# right_revision0_6.net
KiCad netlist of a schematic drawn in EAGLE
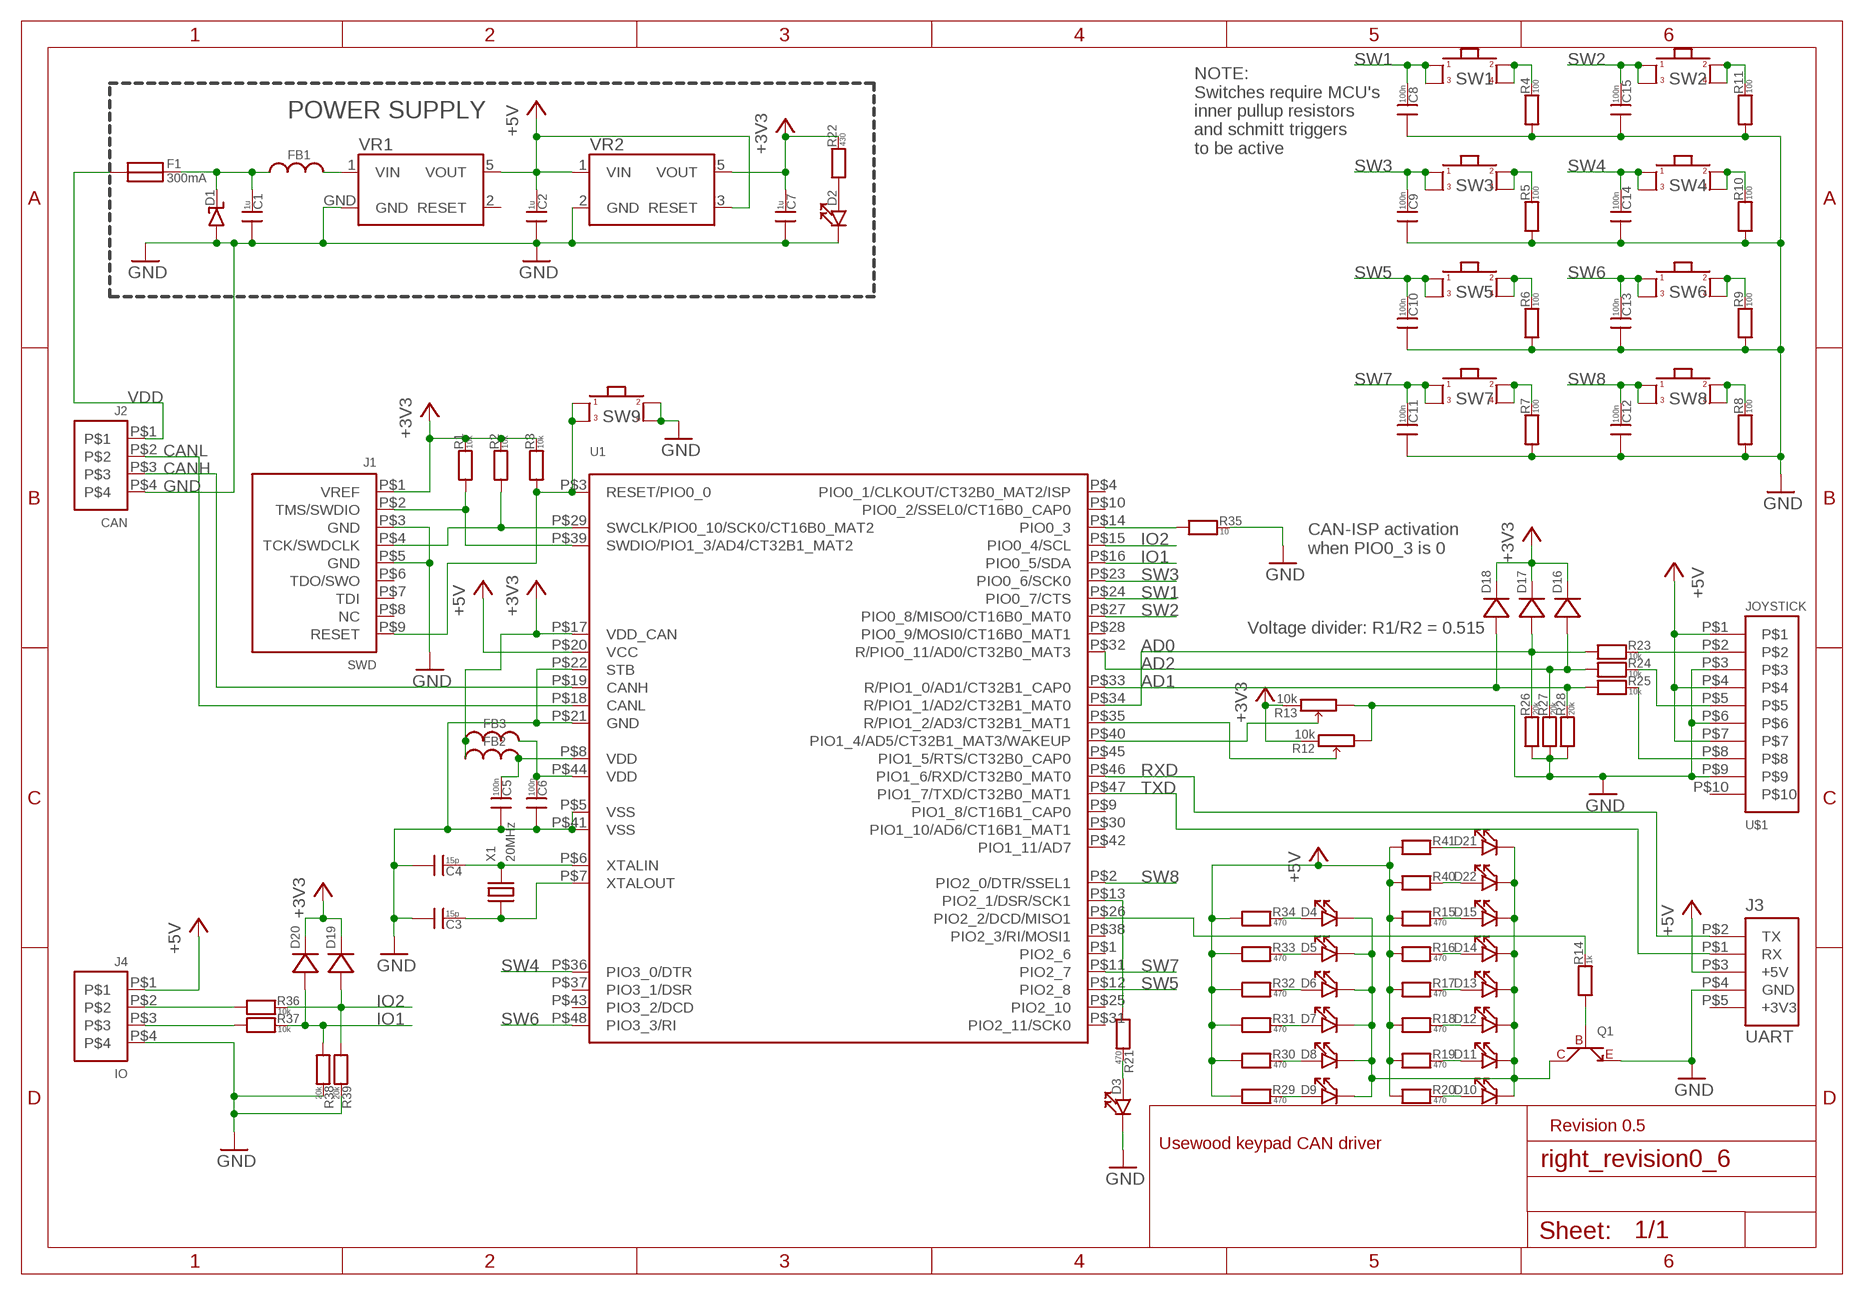
[diagram p0: schematic, sheet 1]

(export (version "E")
  (design (tool "Eeschema 10.0.6"))
  (components
    (comp (ref "C1")
      (value "1u")
      (footprint "eagle-import:0603")
      (libsource (lib "eagle-import") (part "CAP0603"))
    )
    (comp (ref "C2")
      (value "1u")
      (footprint "eagle-import:0603")
      (libsource (lib "eagle-import") (part "CAP0603"))
    )
    (comp (ref "C3")
      (value "15p")
      (footprint "eagle-import:0603")
      (libsource (lib "eagle-import") (part "CAP0603"))
    )
    (comp (ref "C4")
      (value "15p")
      (footprint "eagle-import:0603")
      (libsource (lib "eagle-import") (part "CAP0603"))
    )
    (comp (ref "C5")
      (value "100n")
      (footprint "eagle-import:0603")
      (libsource (lib "eagle-import") (part "CAP0603"))
    )
    (comp (ref "C6")
      (value "100n")
      (footprint "eagle-import:0603")
      (libsource (lib "eagle-import") (part "CAP0603"))
    )
    (comp (ref "C7")
      (value "1u")
      (footprint "eagle-import:0603")
      (libsource (lib "eagle-import") (part "CAP0603"))
    )
    (comp (ref "C8")
      (value "100n")
      (footprint "eagle-import:0603")
      (libsource (lib "eagle-import") (part "CAP0603"))
    )
    (comp (ref "C9")
      (value "100n")
      (footprint "eagle-import:0603")
      (libsource (lib "eagle-import") (part "CAP0603"))
    )
    (comp (ref "C10")
      (value "100n")
      (footprint "eagle-import:0603")
      (libsource (lib "eagle-import") (part "CAP0603"))
    )
    (comp (ref "C11")
      (value "100n")
      (footprint "eagle-import:0603")
      (libsource (lib "eagle-import") (part "CAP0603"))
    )
    (comp (ref "C12")
      (value "100n")
      (footprint "eagle-import:0603")
      (libsource (lib "eagle-import") (part "CAP0603"))
    )
    (comp (ref "C13")
      (value "100n")
      (footprint "eagle-import:0603")
      (libsource (lib "eagle-import") (part "CAP0603"))
    )
    (comp (ref "C14")
      (value "100n")
      (footprint "eagle-import:0603")
      (libsource (lib "eagle-import") (part "CAP0603"))
    )
    (comp (ref "C15")
      (value "100n")
      (footprint "eagle-import:0603")
      (libsource (lib "eagle-import") (part "CAP0603"))
    )
    (comp (ref "D1")
      (value "DIODE_TVSDO-214AA")
      (footprint "eagle-import:DO-214AB")
      (libsource (lib "eagle-import") (part "DIODE_TVSDO-214AA"))
    )
    (comp (ref "D2")
      (value "LED0603")
      (footprint "eagle-import:0603")
      (libsource (lib "eagle-import") (part "LED0603"))
    )
    (comp (ref "D3")
      (value "LED0603")
      (footprint "eagle-import:0603")
      (libsource (lib "eagle-import") (part "LED0603"))
    )
    (comp (ref "D4")
      (value "LED0603")
      (footprint "eagle-import:0603")
      (libsource (lib "eagle-import") (part "LED0603"))
    )
    (comp (ref "D5")
      (value "LED0603")
      (footprint "eagle-import:0603")
      (libsource (lib "eagle-import") (part "LED0603"))
    )
    (comp (ref "D6")
      (value "LED0603")
      (footprint "eagle-import:0603")
      (libsource (lib "eagle-import") (part "LED0603"))
    )
    (comp (ref "D7")
      (value "LED0603")
      (footprint "eagle-import:0603")
      (libsource (lib "eagle-import") (part "LED0603"))
    )
    (comp (ref "D8")
      (value "LED0603")
      (footprint "eagle-import:0603")
      (libsource (lib "eagle-import") (part "LED0603"))
    )
    (comp (ref "D9")
      (value "LED0603")
      (footprint "eagle-import:0603")
      (libsource (lib "eagle-import") (part "LED0603"))
    )
    (comp (ref "D10")
      (value "LED0603")
      (footprint "eagle-import:0603")
      (libsource (lib "eagle-import") (part "LED0603"))
    )
    (comp (ref "D11")
      (value "LED0603")
      (footprint "eagle-import:0603")
      (libsource (lib "eagle-import") (part "LED0603"))
    )
    (comp (ref "D12")
      (value "LED0603")
      (footprint "eagle-import:0603")
      (libsource (lib "eagle-import") (part "LED0603"))
    )
    (comp (ref "D13")
      (value "LED0603")
      (footprint "eagle-import:0603")
      (libsource (lib "eagle-import") (part "LED0603"))
    )
    (comp (ref "D14")
      (value "LED0603")
      (footprint "eagle-import:0603")
      (libsource (lib "eagle-import") (part "LED0603"))
    )
    (comp (ref "D15")
      (value "LED0603")
      (footprint "eagle-import:0603")
      (libsource (lib "eagle-import") (part "LED0603"))
    )
    (comp (ref "D16")
      (value "DIODEDO219AB")
      (footprint "eagle-import:DO219AB")
      (libsource (lib "eagle-import") (part "DIODEDO219AB"))
    )
    (comp (ref "D17")
      (value "DIODEDO219AB")
      (footprint "eagle-import:DO219AB")
      (libsource (lib "eagle-import") (part "DIODEDO219AB"))
    )
    (comp (ref "D18")
      (value "DIODEDO219AB")
      (footprint "eagle-import:DO219AB")
      (libsource (lib "eagle-import") (part "DIODEDO219AB"))
    )
    (comp (ref "D19")
      (value "DIODEDO219AB")
      (footprint "eagle-import:DO219AB")
      (libsource (lib "eagle-import") (part "DIODEDO219AB"))
    )
    (comp (ref "D20")
      (value "DIODEDO219AB")
      (footprint "eagle-import:DO219AB")
      (libsource (lib "eagle-import") (part "DIODEDO219AB"))
    )
    (comp (ref "D21")
      (value "LED0603")
      (footprint "eagle-import:0603")
      (libsource (lib "eagle-import") (part "LED0603"))
    )
    (comp (ref "D22")
      (value "LED0603")
      (footprint "eagle-import:0603")
      (libsource (lib "eagle-import") (part "LED0603"))
    )
    (comp (ref "F1")
      (value "300mA")
      (footprint "eagle-import:FUSE_100MA")
      (libsource (lib "eagle-import") (part "FUSE100MA"))
    )
    (comp (ref "FB1")
      (value "FERRITE0603")
      (footprint "eagle-import:0603")
      (libsource (lib "eagle-import") (part "FERRITE0603"))
    )
    (comp (ref "FB2")
      (value "FERRITE0603")
      (footprint "eagle-import:0603")
      (libsource (lib "eagle-import") (part "FERRITE0603"))
    )
    (comp (ref "FB3")
      (value "FERRITE0603")
      (footprint "eagle-import:0603")
      (libsource (lib "eagle-import") (part "FERRITE0603"))
    )
    (comp (ref "J1")
      (value "SWD")
      (footprint "eagle-import:ARM_10_PIN_JTAG_SWD_CONNECTOR")
      (libsource (lib "eagle-import") (part "ARM_JTAG/SWD_HEADER_10_PINSMD"))
    )
    (comp (ref "J2")
      (value "CAN")
      (footprint "eagle-import:MOLEX_MICRO-FIT_4WAY")
      (libsource (lib "eagle-import") (part "MOLEX_MICRO-FIT_4WAYTH"))
    )
    (comp (ref "J3")
      (value "UART")
      (footprint "eagle-import:HEADER5_1")
      (libsource (lib "eagle-import") (part "HEADER_USARTTH"))
    )
    (comp (ref "J4")
      (value "IO")
      (footprint "eagle-import:MOLEX_MICRO-FIT_4WAY")
      (libsource (lib "eagle-import") (part "MOLEX_MICRO-FIT_4WAYTH"))
    )
    (comp (ref "Q1")
      (value "NPN_TRANSISTORSOT323")
      (footprint "eagle-import:SOT323")
      (libsource (lib "eagle-import") (part "NPN_TRANSISTORSOT323"))
    )
    (comp (ref "R1")
      (value "10k")
      (footprint "eagle-import:0603")
      (libsource (lib "eagle-import") (part "RES0603"))
    )
    (comp (ref "R2")
      (value "10k")
      (footprint "eagle-import:0603")
      (libsource (lib "eagle-import") (part "RES0603"))
    )
    (comp (ref "R3")
      (value "10k")
      (footprint "eagle-import:0603")
      (libsource (lib "eagle-import") (part "RES0603"))
    )
    (comp (ref "R4")
      (value "100")
      (footprint "eagle-import:0603")
      (libsource (lib "eagle-import") (part "RES0603"))
    )
    (comp (ref "R5")
      (value "100")
      (footprint "eagle-import:0603")
      (libsource (lib "eagle-import") (part "RES0603"))
    )
    (comp (ref "R6")
      (value "100")
      (footprint "eagle-import:0603")
      (libsource (lib "eagle-import") (part "RES0603"))
    )
    (comp (ref "R7")
      (value "100")
      (footprint "eagle-import:0603")
      (libsource (lib "eagle-import") (part "RES0603"))
    )
    (comp (ref "R8")
      (value "100")
      (footprint "eagle-import:0603")
      (libsource (lib "eagle-import") (part "RES0603"))
    )
    (comp (ref "R9")
      (value "100")
      (footprint "eagle-import:0603")
      (libsource (lib "eagle-import") (part "RES0603"))
    )
    (comp (ref "R10")
      (value "100")
      (footprint "eagle-import:0603")
      (libsource (lib "eagle-import") (part "RES0603"))
    )
    (comp (ref "R11")
      (value "100")
      (footprint "eagle-import:0603")
      (libsource (lib "eagle-import") (part "RES0603"))
    )
    (comp (ref "R12")
      (value "10k")
      (footprint "eagle-import:RES_POT_RK09K1130C94")
      (libsource (lib "eagle-import") (part "RES_POTRK09K1130C94"))
    )
    (comp (ref "R13")
      (value "10k")
      (footprint "eagle-import:RES_POT_RK09K1130C94")
      (libsource (lib "eagle-import") (part "RES_POTRK09K1130C94"))
    )
    (comp (ref "R14")
      (value "1k")
      (footprint "eagle-import:0603")
      (libsource (lib "eagle-import") (part "RES0603"))
    )
    (comp (ref "R15")
      (value "470")
      (footprint "eagle-import:0603")
      (libsource (lib "eagle-import") (part "RES0603"))
    )
    (comp (ref "R16")
      (value "470")
      (footprint "eagle-import:0603")
      (libsource (lib "eagle-import") (part "RES0603"))
    )
    (comp (ref "R17")
      (value "470")
      (footprint "eagle-import:0603")
      (libsource (lib "eagle-import") (part "RES0603"))
    )
    (comp (ref "R18")
      (value "470")
      (footprint "eagle-import:0603")
      (libsource (lib "eagle-import") (part "RES0603"))
    )
    (comp (ref "R19")
      (value "470")
      (footprint "eagle-import:0603")
      (libsource (lib "eagle-import") (part "RES0603"))
    )
    (comp (ref "R20")
      (value "470")
      (footprint "eagle-import:0603")
      (libsource (lib "eagle-import") (part "RES0603"))
    )
    (comp (ref "R21")
      (value "470")
      (footprint "eagle-import:0603")
      (libsource (lib "eagle-import") (part "RES0603"))
    )
    (comp (ref "R22")
      (value "430")
      (footprint "eagle-import:0603")
      (libsource (lib "eagle-import") (part "RES0603"))
    )
    (comp (ref "R23")
      (value "10k")
      (footprint "eagle-import:0603")
      (libsource (lib "eagle-import") (part "RES0603"))
    )
    (comp (ref "R24")
      (value "10k")
      (footprint "eagle-import:0603")
      (libsource (lib "eagle-import") (part "RES0603"))
    )
    (comp (ref "R25")
      (value "10k")
      (footprint "eagle-import:0603")
      (libsource (lib "eagle-import") (part "RES0603"))
    )
    (comp (ref "R26")
      (value "20k")
      (footprint "eagle-import:0603")
      (libsource (lib "eagle-import") (part "RES0603"))
    )
    (comp (ref "R27")
      (value "20k")
      (footprint "eagle-import:0603")
      (libsource (lib "eagle-import") (part "RES0603"))
    )
    (comp (ref "R28")
      (value "20k")
      (footprint "eagle-import:0603")
      (libsource (lib "eagle-import") (part "RES0603"))
    )
    (comp (ref "R29")
      (value "470")
      (footprint "eagle-import:0603")
      (libsource (lib "eagle-import") (part "RES0603"))
    )
    (comp (ref "R30")
      (value "470")
      (footprint "eagle-import:0603")
      (libsource (lib "eagle-import") (part "RES0603"))
    )
    (comp (ref "R31")
      (value "470")
      (footprint "eagle-import:0603")
      (libsource (lib "eagle-import") (part "RES0603"))
    )
    (comp (ref "R32")
      (value "470")
      (footprint "eagle-import:0603")
      (libsource (lib "eagle-import") (part "RES0603"))
    )
    (comp (ref "R33")
      (value "470")
      (footprint "eagle-import:0603")
      (libsource (lib "eagle-import") (part "RES0603"))
    )
    (comp (ref "R34")
      (value "470")
      (footprint "eagle-import:0603")
      (libsource (lib "eagle-import") (part "RES0603"))
    )
    (comp (ref "R35")
      (value "10")
      (footprint "eagle-import:0603")
      (libsource (lib "eagle-import") (part "RES0603"))
    )
    (comp (ref "R36")
      (value "10k")
      (footprint "eagle-import:0603")
      (libsource (lib "eagle-import") (part "RES0603"))
    )
    (comp (ref "R37")
      (value "10k")
      (footprint "eagle-import:0603")
      (libsource (lib "eagle-import") (part "RES0603"))
    )
    (comp (ref "R38")
      (value "20k")
      (footprint "eagle-import:0603")
      (libsource (lib "eagle-import") (part "RES0603"))
    )
    (comp (ref "R39")
      (value "20k")
      (footprint "eagle-import:0603")
      (libsource (lib "eagle-import") (part "RES0603"))
    )
    (comp (ref "R40")
      (value "RES0603")
      (footprint "eagle-import:0603")
      (libsource (lib "eagle-import") (part "RES0603"))
    )
    (comp (ref "R41")
      (value "RES0603")
      (footprint "eagle-import:0603")
      (libsource (lib "eagle-import") (part "RES0603"))
    )
    (comp (ref "SW1")
      (value "SWITCH12X12MM_CENTER_HOLE")
      (footprint "eagle-import:SWITCH_12X12MM_CENTER_HOLE")
      (libsource (lib "eagle-import") (part "SWITCH12X12MM_CENTER_HOLE"))
    )
    (comp (ref "SW2")
      (value "SWITCH12X12MM_CENTER_HOLE")
      (footprint "eagle-import:SWITCH_12X12MM_CENTER_HOLE")
      (libsource (lib "eagle-import") (part "SWITCH12X12MM_CENTER_HOLE"))
    )
    (comp (ref "SW3")
      (value "SWITCH12X12MM_CENTER_HOLE")
      (footprint "eagle-import:SWITCH_12X12MM_CENTER_HOLE")
      (libsource (lib "eagle-import") (part "SWITCH12X12MM_CENTER_HOLE"))
    )
    (comp (ref "SW4")
      (value "SWITCH12X12MM_CENTER_HOLE")
      (footprint "eagle-import:SWITCH_12X12MM_CENTER_HOLE")
      (libsource (lib "eagle-import") (part "SWITCH12X12MM_CENTER_HOLE"))
    )
    (comp (ref "SW5")
      (value "SWITCH12X12MM_CENTER_HOLE")
      (footprint "eagle-import:SWITCH_12X12MM_CENTER_HOLE")
      (libsource (lib "eagle-import") (part "SWITCH12X12MM_CENTER_HOLE"))
    )
    (comp (ref "SW6")
      (value "SWITCH12X12MM_CENTER_HOLE")
      (footprint "eagle-import:SWITCH_12X12MM_CENTER_HOLE")
      (libsource (lib "eagle-import") (part "SWITCH12X12MM_CENTER_HOLE"))
    )
    (comp (ref "SW7")
      (value "SWITCH12X12MM_CENTER_HOLE")
      (footprint "eagle-import:SWITCH_12X12MM_CENTER_HOLE")
      (libsource (lib "eagle-import") (part "SWITCH12X12MM_CENTER_HOLE"))
    )
    (comp (ref "SW8")
      (value "SWITCH12X12MM_CENTER_HOLE")
      (footprint "eagle-import:SWITCH_12X12MM_CENTER_HOLE")
      (libsource (lib "eagle-import") (part "SWITCH12X12MM_CENTER_HOLE"))
    )
    (comp (ref "SW9")
      (value "SWITCHREGULAR")
      (footprint "eagle-import:SWITCH_REGULAR")
      (libsource (lib "eagle-import") (part "SWITCHREGULAR"))
    )
    (comp (ref "U$1")
      (value "JOYSTICK")
      (footprint "eagle-import:MOLEX-MICRO-FIT_10WAY")
      (libsource (lib "eagle-import") (part "MOLEX_MICRO-FIT_10WAYTH"))
    )
    (comp (ref "U1")
      (value "LPC11C22QFP48")
      (footprint "eagle-import:QFP48")
      (libsource (lib "eagle-import") (part "LPC11C22QFP48"))
    )
    (comp (ref "VR1")
      (value "NCV8675175AA")
      (footprint "eagle-import:175AA")
      (libsource (lib "eagle-import") (part "NCV8675175AA"))
    )
    (comp (ref "VR2")
      (value "LP2985SOP5")
      (footprint "eagle-import:SOP5")
      (libsource (lib "eagle-import") (part "LP2985SOP5"))
    )
    (comp (ref "X1")
      (value "20MHz")
      (footprint "eagle-import:XTAL_SMD_5X3.2")
      (libsource (lib "eagle-import") (part "XTALSMD_5X3.2"))
    )
  )
  (nets
    (net (code "1") (name "+3V3") (class "Default")
      (node (ref "C7") (pin "1") (pinfunction "P$2_1") (pintype "bidirectional"))
      (node (ref "D16") (pin "P$2") (pinfunction "N_P$2") (pintype "bidirectional"))
      (node (ref "D17") (pin "P$2") (pinfunction "N_P$2") (pintype "bidirectional"))
      (node (ref "D18") (pin "P$2") (pinfunction "N_P$2") (pintype "bidirectional"))
      (node (ref "D19") (pin "P$2") (pinfunction "N_P$2") (pintype "bidirectional"))
      (node (ref "D20") (pin "P$2") (pinfunction "N_P$2") (pintype "bidirectional"))
      (node (ref "FB2") (pin "0") (pinfunction "P$1_0") (pintype "bidirectional"))
      (node (ref "FB3") (pin "0") (pinfunction "P$1_0") (pintype "bidirectional"))
      (node (ref "J1") (pin "P$1") (pinfunction "VREF_P$1") (pintype "bidirectional"))
      (node (ref "R1") (pin "1") (pinfunction "P$2_1") (pintype "bidirectional"))
      (node (ref "R12") (pin "P$3") (pinfunction "P$2_P$3") (pintype "bidirectional"))
      (node (ref "R13") (pin "P$3") (pinfunction "P$2_P$3") (pintype "bidirectional"))
      (node (ref "R2") (pin "1") (pinfunction "P$2_1") (pintype "bidirectional"))
      (node (ref "R22") (pin "1") (pinfunction "P$2_1") (pintype "bidirectional"))
      (node (ref "R3") (pin "1") (pinfunction "P$2_1") (pintype "bidirectional"))
      (node (ref "U1") (pin "P$17") (pinfunction "VDD_CAN_P$17") (pintype "bidirectional"))
      (node (ref "VR2") (pin "5") (pinfunction "VOUT_5") (pintype "bidirectional"))
    )
    (net (code "2") (name "+5V") (class "Default")
      (node (ref "C2") (pin "1") (pinfunction "P$2_1") (pintype "bidirectional"))
      (node (ref "J3") (pin "P$3") (pinfunction "+5V_P$3") (pintype "bidirectional"))
      (node (ref "J4") (pin "P$1") (pinfunction "P$1_P$1") (pintype "bidirectional"))
      (node (ref "R15") (pin "0") (pinfunction "P$1_0") (pintype "bidirectional"))
      (node (ref "R16") (pin "0") (pinfunction "P$1_0") (pintype "bidirectional"))
      (node (ref "R17") (pin "0") (pinfunction "P$1_0") (pintype "bidirectional"))
      (node (ref "R18") (pin "0") (pinfunction "P$1_0") (pintype "bidirectional"))
      (node (ref "R19") (pin "0") (pinfunction "P$1_0") (pintype "bidirectional"))
      (node (ref "R20") (pin "0") (pinfunction "P$1_0") (pintype "bidirectional"))
      (node (ref "R29") (pin "0") (pinfunction "P$1_0") (pintype "bidirectional"))
      (node (ref "R30") (pin "0") (pinfunction "P$1_0") (pintype "bidirectional"))
      (node (ref "R31") (pin "0") (pinfunction "P$1_0") (pintype "bidirectional"))
      (node (ref "R32") (pin "0") (pinfunction "P$1_0") (pintype "bidirectional"))
      (node (ref "R33") (pin "0") (pinfunction "P$1_0") (pintype "bidirectional"))
      (node (ref "R34") (pin "0") (pinfunction "P$1_0") (pintype "bidirectional"))
      (node (ref "R40") (pin "0") (pinfunction "P$1_0") (pintype "bidirectional"))
      (node (ref "R41") (pin "0") (pinfunction "P$1_0") (pintype "bidirectional"))
      (node (ref "U$1") (pin "P$1") (pinfunction "P$1_P$1") (pintype "bidirectional"))
      (node (ref "U$1") (pin "P$4") (pinfunction "P$4_P$4") (pintype "bidirectional"))
      (node (ref "U$1") (pin "P$7") (pinfunction "P$7_P$7") (pintype "bidirectional"))
      (node (ref "U1") (pin "P$20") (pinfunction "VCC_P$20") (pintype "bidirectional"))
      (node (ref "VR1") (pin "5") (pinfunction "VOUT_5") (pintype "bidirectional"))
      (node (ref "VR2") (pin "1") (pinfunction "VIN_1") (pintype "bidirectional"))
      (node (ref "VR2") (pin "3") (pinfunction "RESET_3") (pintype "bidirectional"))
    )
    (net (code "3") (name "/AD0") (class "Default")
      (node (ref "D17") (pin "P$1") (pinfunction "P_P$1") (pintype "bidirectional"))
      (node (ref "R23") (pin "0") (pinfunction "P$1_0") (pintype "bidirectional"))
      (node (ref "R26") (pin "1") (pinfunction "P$2_1") (pintype "bidirectional"))
      (node (ref "U1") (pin "P$34") (pinfunction "R/PIO1_1/AD2/CT32B1_MAT0_P$34") (pintype "bidirectional"))
    )
    (net (code "4") (name "/AD1") (class "Default")
      (node (ref "D18") (pin "P$1") (pinfunction "P_P$1") (pintype "bidirectional"))
      (node (ref "R25") (pin "0") (pinfunction "P$1_0") (pintype "bidirectional"))
      (node (ref "R28") (pin "1") (pinfunction "P$2_1") (pintype "bidirectional"))
      (node (ref "U1") (pin "P$33") (pinfunction "R/PIO1_0/AD1/CT32B1_CAP0_P$33") (pintype "bidirectional"))
    )
    (net (code "5") (name "/AD2") (class "Default")
      (node (ref "D16") (pin "P$1") (pinfunction "P_P$1") (pintype "bidirectional"))
      (node (ref "R24") (pin "0") (pinfunction "P$1_0") (pintype "bidirectional"))
      (node (ref "R27") (pin "1") (pinfunction "P$2_1") (pintype "bidirectional"))
      (node (ref "U1") (pin "P$32") (pinfunction "R/PIO0_11/AD0/CT32B0_MAT3_P$32") (pintype "bidirectional"))
    )
    (net (code "6") (name "/CANH") (class "Default")
      (node (ref "J2") (pin "P$3") (pinfunction "P$3_P$3") (pintype "bidirectional"))
      (node (ref "U1") (pin "P$19") (pinfunction "CANH_P$19") (pintype "bidirectional"))
    )
    (net (code "7") (name "/CANL") (class "Default")
      (node (ref "J2") (pin "P$2") (pinfunction "P$2_P$2") (pintype "bidirectional"))
      (node (ref "U1") (pin "P$18") (pinfunction "CANL_P$18") (pintype "bidirectional"))
    )
    (net (code "8") (name "/IO1") (class "Default")
      (node (ref "D20") (pin "P$1") (pinfunction "P_P$1") (pintype "bidirectional"))
      (node (ref "R37") (pin "1") (pinfunction "P$2_1") (pintype "bidirectional"))
      (node (ref "R38") (pin "0") (pinfunction "P$1_0") (pintype "bidirectional"))
      (node (ref "U1") (pin "P$16") (pinfunction "PIO0_5/SDA_P$16") (pintype "bidirectional"))
    )
    (net (code "9") (name "/IO2") (class "Default")
      (node (ref "D19") (pin "P$1") (pinfunction "P_P$1") (pintype "bidirectional"))
      (node (ref "R36") (pin "1") (pinfunction "P$2_1") (pintype "bidirectional"))
      (node (ref "R39") (pin "0") (pinfunction "P$1_0") (pintype "bidirectional"))
      (node (ref "U1") (pin "P$15") (pinfunction "PIO0_4/SCL_P$15") (pintype "bidirectional"))
    )
    (net (code "10") (name "/RXD") (class "Default")
      (node (ref "J3") (pin "P$2") (pinfunction "TX_P$2") (pintype "bidirectional"))
      (node (ref "U1") (pin "P$46") (pinfunction "PIO1_6/RXD/CT32B0_MAT0_P$46") (pintype "bidirectional"))
    )
    (net (code "11") (name "/SW1") (class "Default")
      (node (ref "C8") (pin "1") (pinfunction "P$2_1") (pintype "bidirectional"))
      (node (ref "SW1") (pin "P$1") (pinfunction "P$1_P$1") (pintype "bidirectional"))
      (node (ref "SW1") (pin "P$2") (pinfunction "P$3_P$2") (pintype "bidirectional"))
      (node (ref "U1") (pin "P$24") (pinfunction "PIO0_7/CTS_P$24") (pintype "bidirectional"))
    )
    (net (code "12") (name "/SW2") (class "Default")
      (node (ref "C15") (pin "1") (pinfunction "P$2_1") (pintype "bidirectional"))
      (node (ref "SW2") (pin "P$1") (pinfunction "P$1_P$1") (pintype "bidirectional"))
      (node (ref "SW2") (pin "P$2") (pinfunction "P$3_P$2") (pintype "bidirectional"))
      (node (ref "U1") (pin "P$27") (pinfunction "PIO0_8/MISO0/CT16B0_MAT0_P$27") (pintype "bidirectional"))
    )
    (net (code "13") (name "/SW3") (class "Default")
      (node (ref "C9") (pin "1") (pinfunction "P$2_1") (pintype "bidirectional"))
      (node (ref "SW3") (pin "P$1") (pinfunction "P$1_P$1") (pintype "bidirectional"))
      (node (ref "SW3") (pin "P$2") (pinfunction "P$3_P$2") (pintype "bidirectional"))
      (node (ref "U1") (pin "P$23") (pinfunction "PIO0_6/SCK0_P$23") (pintype "bidirectional"))
    )
    (net (code "14") (name "/SW4") (class "Default")
      (node (ref "C14") (pin "1") (pinfunction "P$2_1") (pintype "bidirectional"))
      (node (ref "SW4") (pin "P$1") (pinfunction "P$1_P$1") (pintype "bidirectional"))
      (node (ref "SW4") (pin "P$2") (pinfunction "P$3_P$2") (pintype "bidirectional"))
      (node (ref "U1") (pin "P$36") (pinfunction "PIO3_0/DTR_P$36") (pintype "bidirectional"))
    )
    (net (code "15") (name "/SW5") (class "Default")
      (node (ref "C10") (pin "1") (pinfunction "P$2_1") (pintype "bidirectional"))
      (node (ref "SW5") (pin "P$1") (pinfunction "P$1_P$1") (pintype "bidirectional"))
      (node (ref "SW5") (pin "P$2") (pinfunction "P$3_P$2") (pintype "bidirectional"))
      (node (ref "U1") (pin "P$12") (pinfunction "PIO2_8_P$12") (pintype "bidirectional"))
    )
    (net (code "16") (name "/SW6") (class "Default")
      (node (ref "C13") (pin "1") (pinfunction "P$2_1") (pintype "bidirectional"))
      (node (ref "SW6") (pin "P$1") (pinfunction "P$1_P$1") (pintype "bidirectional"))
      (node (ref "SW6") (pin "P$2") (pinfunction "P$3_P$2") (pintype "bidirectional"))
      (node (ref "U1") (pin "P$48") (pinfunction "PIO3_3/RI_P$48") (pintype "bidirectional"))
    )
    (net (code "17") (name "/SW7") (class "Default")
      (node (ref "C11") (pin "1") (pinfunction "P$2_1") (pintype "bidirectional"))
      (node (ref "SW7") (pin "P$1") (pinfunction "P$1_P$1") (pintype "bidirectional"))
      (node (ref "SW7") (pin "P$2") (pinfunction "P$3_P$2") (pintype "bidirectional"))
      (node (ref "U1") (pin "P$11") (pinfunction "PIO2_7_P$11") (pintype "bidirectional"))
    )
    (net (code "18") (name "/SW8") (class "Default")
      (node (ref "C12") (pin "1") (pinfunction "P$2_1") (pintype "bidirectional"))
      (node (ref "SW8") (pin "P$1") (pinfunction "P$1_P$1") (pintype "bidirectional"))
      (node (ref "SW8") (pin "P$2") (pinfunction "P$3_P$2") (pintype "bidirectional"))
      (node (ref "U1") (pin "P$2") (pinfunction "PIO2_0/DTR/SSEL1_P$2") (pintype "bidirectional"))
    )
    (net (code "19") (name "/TXD") (class "Default")
      (node (ref "J3") (pin "P$1") (pinfunction "RX_P$1") (pintype "bidirectional"))
      (node (ref "U1") (pin "P$47") (pinfunction "PIO1_7/TXD/CT32B0_MAT1_P$47") (pintype "bidirectional"))
    )
    (net (code "20") (name "/VDD") (class "Default")
      (node (ref "F1") (pin "P$1") (pinfunction "P$1_P$1") (pintype "bidirectional"))
      (node (ref "J2") (pin "P$1") (pinfunction "P$1_P$1") (pintype "bidirectional"))
    )
    (net (code "21") (name "GND") (class "Default")
      (node (ref "C1") (pin "0") (pinfunction "P$1_0") (pintype "bidirectional"))
      (node (ref "C10") (pin "0") (pinfunction "P$1_0") (pintype "bidirectional"))
      (node (ref "C11") (pin "0") (pinfunction "P$1_0") (pintype "bidirectional"))
      (node (ref "C12") (pin "0") (pinfunction "P$1_0") (pintype "bidirectional"))
      (node (ref "C13") (pin "0") (pinfunction "P$1_0") (pintype "bidirectional"))
      (node (ref "C14") (pin "0") (pinfunction "P$1_0") (pintype "bidirectional"))
      (node (ref "C15") (pin "0") (pinfunction "P$1_0") (pintype "bidirectional"))
      (node (ref "C2") (pin "0") (pinfunction "P$1_0") (pintype "bidirectional"))
      (node (ref "C3") (pin "0") (pinfunction "P$1_0") (pintype "bidirectional"))
      (node (ref "C4") (pin "0") (pinfunction "P$1_0") (pintype "bidirectional"))
      (node (ref "C5") (pin "0") (pinfunction "P$1_0") (pintype "bidirectional"))
      (node (ref "C6") (pin "0") (pinfunction "P$1_0") (pintype "bidirectional"))
      (node (ref "C7") (pin "0") (pinfunction "P$1_0") (pintype "bidirectional"))
      (node (ref "C8") (pin "0") (pinfunction "P$1_0") (pintype "bidirectional"))
      (node (ref "C9") (pin "0") (pinfunction "P$1_0") (pintype "bidirectional"))
      (node (ref "D1") (pin "P$1") (pinfunction "P_P$1") (pintype "bidirectional"))
      (node (ref "D2") (pin "1") (pinfunction "1_1") (pintype "bidirectional"))
      (node (ref "D3") (pin "1") (pinfunction "1_1") (pintype "bidirectional"))
      (node (ref "J1") (pin "P$3") (pinfunction "GND_P$3") (pintype "bidirectional"))
      (node (ref "J1") (pin "P$5") (pinfunction "GND_P$5") (pintype "bidirectional"))
      (node (ref "J2") (pin "P$4") (pinfunction "P$4_P$4") (pintype "bidirectional"))
      (node (ref "J3") (pin "P$4") (pinfunction "GND_P$4") (pintype "bidirectional"))
      (node (ref "J4") (pin "P$4") (pinfunction "P$4_P$4") (pintype "bidirectional"))
      (node (ref "Q1") (pin "R") (pinfunction "E_R") (pintype "bidirectional"))
      (node (ref "R10") (pin "0") (pinfunction "P$1_0") (pintype "bidirectional"))
      (node (ref "R11") (pin "0") (pinfunction "P$1_0") (pintype "bidirectional"))
      (node (ref "R12") (pin "P$1") (pinfunction "P$1_P$1") (pintype "bidirectional"))
      (node (ref "R13") (pin "P$1") (pinfunction "P$1_P$1") (pintype "bidirectional"))
      (node (ref "R26") (pin "0") (pinfunction "P$1_0") (pintype "bidirectional"))
      (node (ref "R27") (pin "0") (pinfunction "P$1_0") (pintype "bidirectional"))
      (node (ref "R28") (pin "0") (pinfunction "P$1_0") (pintype "bidirectional"))
      (node (ref "R35") (pin "1") (pinfunction "P$2_1") (pintype "bidirectional"))
      (node (ref "R38") (pin "1") (pinfunction "P$2_1") (pintype "bidirectional"))
      (node (ref "R39") (pin "1") (pinfunction "P$2_1") (pintype "bidirectional"))
      (node (ref "R4") (pin "0") (pinfunction "P$1_0") (pintype "bidirectional"))
      (node (ref "R5") (pin "0") (pinfunction "P$1_0") (pintype "bidirectional"))
      (node (ref "R6") (pin "0") (pinfunction "P$1_0") (pintype "bidirectional"))
      (node (ref "R7") (pin "0") (pinfunction "P$1_0") (pintype "bidirectional"))
      (node (ref "R8") (pin "0") (pinfunction "P$1_0") (pintype "bidirectional"))
      (node (ref "R9") (pin "0") (pinfunction "P$1_0") (pintype "bidirectional"))
      (node (ref "SW9") (pin "P$3") (pinfunction "P$4_P$3") (pintype "bidirectional"))
      (node (ref "SW9") (pin "P$4") (pinfunction "P$2_P$4") (pintype "bidirectional"))
      (node (ref "U$1") (pin "P$3") (pinfunction "P$3_P$3") (pintype "bidirectional"))
      (node (ref "U$1") (pin "P$6") (pinfunction "P$6_P$6") (pintype "bidirectional"))
      (node (ref "U$1") (pin "P$9") (pinfunction "P$9_P$9") (pintype "bidirectional"))
      (node (ref "U1") (pin "P$21") (pinfunction "GND_P$21") (pintype "bidirectional"))
      (node (ref "U1") (pin "P$22") (pinfunction "STB_P$22") (pintype "bidirectional"))
      (node (ref "U1") (pin "P$41") (pinfunction "VSS_P$41") (pintype "bidirectional"))
      (node (ref "U1") (pin "P$5") (pinfunction "VSS_P$5") (pintype "bidirectional"))
      (node (ref "VR1") (pin "GND") (pinfunction "GND_GND") (pintype "bidirectional"))
      (node (ref "VR2") (pin "2") (pinfunction "GND_2") (pintype "bidirectional"))
    )
    (net (code "22") (name "Net-(C1-P$2)") (class "Default")
      (node (ref "C1") (pin "1") (pinfunction "P$2_1") (pintype "bidirectional"))
      (node (ref "D1") (pin "P$2") (pinfunction "N_P$2") (pintype "bidirectional"))
      (node (ref "F1") (pin "P$2") (pinfunction "P$2_P$2") (pintype "bidirectional"))
      (node (ref "FB1") (pin "0") (pinfunction "P$1_0") (pintype "bidirectional"))
    )
    (net (code "23") (name "Net-(C3-P$2)") (class "Default")
      (node (ref "C3") (pin "1") (pinfunction "P$2_1") (pintype "bidirectional"))
      (node (ref "U1") (pin "P$7") (pinfunction "XTALOUT_P$7") (pintype "bidirectional"))
      (node (ref "X1") (pin "P$1") (pinfunction "P$1_P$1") (pintype "bidirectional"))
    )
    (net (code "24") (name "Net-(C4-P$2)") (class "Default")
      (node (ref "C4") (pin "1") (pinfunction "P$2_1") (pintype "bidirectional"))
      (node (ref "U1") (pin "P$6") (pinfunction "XTALIN_P$6") (pintype "bidirectional"))
      (node (ref "X1") (pin "P$2") (pinfunction "P$2_P$2") (pintype "bidirectional"))
    )
    (net (code "25") (name "Net-(C5-P$2)") (class "Default")
      (node (ref "C5") (pin "1") (pinfunction "P$2_1") (pintype "bidirectional"))
      (node (ref "FB2") (pin "1") (pinfunction "P$2_1") (pintype "bidirectional"))
      (node (ref "U1") (pin "P$8") (pinfunction "VDD_P$8") (pintype "bidirectional"))
    )
    (net (code "26") (name "Net-(C6-P$2)") (class "Default")
      (node (ref "C6") (pin "1") (pinfunction "P$2_1") (pintype "bidirectional"))
      (node (ref "FB3") (pin "1") (pinfunction "P$2_1") (pintype "bidirectional"))
      (node (ref "U1") (pin "P$44") (pinfunction "VDD_P$44") (pintype "bidirectional"))
    )
    (net (code "27") (name "Net-(FB1-P$2)") (class "Default")
      (node (ref "FB1") (pin "1") (pinfunction "P$2_1") (pintype "bidirectional"))
      (node (ref "VR1") (pin "1") (pinfunction "VIN_1") (pintype "bidirectional"))
    )
    (net (code "28") (name "Net-(J1-RESET)") (class "Default")
      (node (ref "J1") (pin "P$9") (pinfunction "RESET_P$9") (pintype "bidirectional"))
      (node (ref "R3") (pin "0") (pinfunction "P$1_0") (pintype "bidirectional"))
      (node (ref "SW9") (pin "P$1") (pinfunction "P$1_P$1") (pintype "bidirectional"))
      (node (ref "SW9") (pin "P$2") (pinfunction "P$3_P$2") (pintype "bidirectional"))
      (node (ref "U1") (pin "P$3") (pinfunction "RESET/PIO0_0_P$3") (pintype "bidirectional"))
    )
    (net (code "29") (name "Net-(J1-TCK{slash}SWDCLK)") (class "Default")
      (node (ref "J1") (pin "P$4") (pinfunction "TCK/SWDCLK_P$4") (pintype "bidirectional"))
      (node (ref "R2") (pin "0") (pinfunction "P$1_0") (pintype "bidirectional"))
      (node (ref "U1") (pin "P$29") (pinfunction "SWCLK/PIO0_10/SCK0/CT16B0_MAT2_P$29") (pintype "bidirectional"))
    )
    (net (code "30") (name "Net-(J1-TMS{slash}SWDIO)") (class "Default")
      (node (ref "J1") (pin "P$2") (pinfunction "TMS/SWDIO_P$2") (pintype "bidirectional"))
      (node (ref "R1") (pin "0") (pinfunction "P$1_0") (pintype "bidirectional"))
      (node (ref "U1") (pin "P$39") (pinfunction "SWDIO/PIO1_3/AD4/CT32B1_MAT2_P$39") (pintype "bidirectional"))
    )
    (net (code "31") (name "Net-(Q1-B)") (class "Default")
      (node (ref "Q1") (pin "L") (pinfunction "B_L") (pintype "bidirectional"))
      (node (ref "R14") (pin "0") (pinfunction "P$1_0") (pintype "bidirectional"))
    )
    (net (code "32") (name "Net-(Q1-C)") (class "Default")
      (node (ref "D10") (pin "1") (pinfunction "1_1") (pintype "bidirectional"))
      (node (ref "D11") (pin "1") (pinfunction "1_1") (pintype "bidirectional"))
      (node (ref "D12") (pin "1") (pinfunction "1_1") (pintype "bidirectional"))
      (node (ref "D13") (pin "1") (pinfunction "1_1") (pintype "bidirectional"))
      (node (ref "D14") (pin "1") (pinfunction "1_1") (pintype "bidirectional"))
      (node (ref "D15") (pin "1") (pinfunction "1_1") (pintype "bidirectional"))
      (node (ref "D21") (pin "1") (pinfunction "1_1") (pintype "bidirectional"))
      (node (ref "D22") (pin "1") (pinfunction "1_1") (pintype "bidirectional"))
      (node (ref "D4") (pin "1") (pinfunction "1_1") (pintype "bidirectional"))
      (node (ref "D5") (pin "1") (pinfunction "1_1") (pintype "bidirectional"))
      (node (ref "D6") (pin "1") (pinfunction "1_1") (pintype "bidirectional"))
      (node (ref "D7") (pin "1") (pinfunction "1_1") (pintype "bidirectional"))
      (node (ref "D8") (pin "1") (pinfunction "1_1") (pintype "bidirectional"))
      (node (ref "D9") (pin "1") (pinfunction "1_1") (pintype "bidirectional"))
      (node (ref "Q1") (pin "M") (pinfunction "C_M") (pintype "bidirectional"))
    )
    (net (code "33") (name "Net-(R4-P$2)") (class "Default")
      (node (ref "R4") (pin "1") (pinfunction "P$2_1") (pintype "bidirectional"))
      (node (ref "SW1") (pin "P$3") (pinfunction "P$2_P$3") (pintype "bidirectional"))
      (node (ref "SW1") (pin "P$4") (pinfunction "P$4_P$4") (pintype "bidirectional"))
    )
    (net (code "34") (name "Net-(R5-P$2)") (class "Default")
      (node (ref "R5") (pin "1") (pinfunction "P$2_1") (pintype "bidirectional"))
      (node (ref "SW3") (pin "P$3") (pinfunction "P$2_P$3") (pintype "bidirectional"))
      (node (ref "SW3") (pin "P$4") (pinfunction "P$4_P$4") (pintype "bidirectional"))
    )
    (net (code "35") (name "Net-(R6-P$2)") (class "Default")
      (node (ref "R6") (pin "1") (pinfunction "P$2_1") (pintype "bidirectional"))
      (node (ref "SW5") (pin "P$3") (pinfunction "P$2_P$3") (pintype "bidirectional"))
      (node (ref "SW5") (pin "P$4") (pinfunction "P$4_P$4") (pintype "bidirectional"))
    )
    (net (code "36") (name "Net-(R7-P$2)") (class "Default")
      (node (ref "R7") (pin "1") (pinfunction "P$2_1") (pintype "bidirectional"))
      (node (ref "SW7") (pin "P$3") (pinfunction "P$2_P$3") (pintype "bidirectional"))
      (node (ref "SW7") (pin "P$4") (pinfunction "P$4_P$4") (pintype "bidirectional"))
    )
    (net (code "37") (name "Net-(R8-P$2)") (class "Default")
      (node (ref "R8") (pin "1") (pinfunction "P$2_1") (pintype "bidirectional"))
      (node (ref "SW8") (pin "P$3") (pinfunction "P$2_P$3") (pintype "bidirectional"))
      (node (ref "SW8") (pin "P$4") (pinfunction "P$4_P$4") (pintype "bidirectional"))
    )
    (net (code "38") (name "Net-(R9-P$2)") (class "Default")
      (node (ref "R9") (pin "1") (pinfunction "P$2_1") (pintype "bidirectional"))
      (node (ref "SW6") (pin "P$3") (pinfunction "P$2_P$3") (pintype "bidirectional"))
      (node (ref "SW6") (pin "P$4") (pinfunction "P$4_P$4") (pintype "bidirectional"))
    )
    (net (code "39") (name "Net-(R10-P$2)") (class "Default")
      (node (ref "R10") (pin "1") (pinfunction "P$2_1") (pintype "bidirectional"))
      (node (ref "SW4") (pin "P$3") (pinfunction "P$2_P$3") (pintype "bidirectional"))
      (node (ref "SW4") (pin "P$4") (pinfunction "P$4_P$4") (pintype "bidirectional"))
    )
    (net (code "40") (name "Net-(R11-P$2)") (class "Default")
      (node (ref "R11") (pin "1") (pinfunction "P$2_1") (pintype "bidirectional"))
      (node (ref "SW2") (pin "P$3") (pinfunction "P$2_P$3") (pintype "bidirectional"))
      (node (ref "SW2") (pin "P$4") (pinfunction "P$4_P$4") (pintype "bidirectional"))
    )
    (net (code "41") (name "Net-(R12-P$3)") (class "Default")
      (node (ref "R12") (pin "P$2") (pinfunction "P$3_P$2") (pintype "bidirectional"))
      (node (ref "U1") (pin "P$35") (pinfunction "R/PIO1_2/AD3/CT32B1_MAT1_P$35") (pintype "bidirectional"))
    )
    (net (code "42") (name "Net-(R13-P$3)") (class "Default")
      (node (ref "R13") (pin "P$2") (pinfunction "P$3_P$2") (pintype "bidirectional"))
      (node (ref "U1") (pin "P$40") (pinfunction "PIO1_4/AD5/CT32B1_MAT3/WAKEUP_P$40") (pintype "bidirectional"))
    )
    (net (code "43") (name "Net-(R14-P$2)") (class "Default")
      (node (ref "R14") (pin "1") (pinfunction "P$2_1") (pintype "bidirectional"))
      (node (ref "U1") (pin "P$26") (pinfunction "PIO2_2/DCD/MISO1_P$26") (pintype "bidirectional"))
    )
    (net (code "44") (name "Net-(R15-P$2)") (class "Default")
      (node (ref "D15") (pin "0") (pinfunction "0_0") (pintype "bidirectional"))
      (node (ref "R15") (pin "1") (pinfunction "P$2_1") (pintype "bidirectional"))
    )
    (net (code "45") (name "Net-(R16-P$2)") (class "Default")
      (node (ref "D14") (pin "0") (pinfunction "0_0") (pintype "bidirectional"))
      (node (ref "R16") (pin "1") (pinfunction "P$2_1") (pintype "bidirectional"))
    )
    (net (code "46") (name "Net-(R17-P$2)") (class "Default")
      (node (ref "D13") (pin "0") (pinfunction "0_0") (pintype "bidirectional"))
      (node (ref "R17") (pin "1") (pinfunction "P$2_1") (pintype "bidirectional"))
    )
    (net (code "47") (name "Net-(R18-P$2)") (class "Default")
      (node (ref "D12") (pin "0") (pinfunction "0_0") (pintype "bidirectional"))
      (node (ref "R18") (pin "1") (pinfunction "P$2_1") (pintype "bidirectional"))
    )
    (net (code "48") (name "Net-(R19-P$2)") (class "Default")
      (node (ref "D11") (pin "0") (pinfunction "0_0") (pintype "bidirectional"))
      (node (ref "R19") (pin "1") (pinfunction "P$2_1") (pintype "bidirectional"))
    )
    (net (code "49") (name "Net-(R20-P$2)") (class "Default")
      (node (ref "D10") (pin "0") (pinfunction "0_0") (pintype "bidirectional"))
      (node (ref "R20") (pin "1") (pinfunction "P$2_1") (pintype "bidirectional"))
    )
    (net (code "50") (name "Net-(R21-P$1)") (class "Default")
      (node (ref "R21") (pin "0") (pinfunction "P$1_0") (pintype "bidirectional"))
      (node (ref "U1") (pin "P$13") (pinfunction "PIO2_1/DSR/SCK1_P$13") (pintype "bidirectional"))
    )
    (net (code "51") (name "Net-(R21-P$2)") (class "Default")
      (node (ref "D3") (pin "0") (pinfunction "0_0") (pintype "bidirectional"))
      (node (ref "R21") (pin "1") (pinfunction "P$2_1") (pintype "bidirectional"))
    )
    (net (code "52") (name "Net-(R22-P$1)") (class "Default")
      (node (ref "D2") (pin "0") (pinfunction "0_0") (pintype "bidirectional"))
      (node (ref "R22") (pin "0") (pinfunction "P$1_0") (pintype "bidirectional"))
    )
    (net (code "53") (name "Net-(R23-P$2)") (class "Default")
      (node (ref "R23") (pin "1") (pinfunction "P$2_1") (pintype "bidirectional"))
      (node (ref "U$1") (pin "P$2") (pinfunction "P$2_P$2") (pintype "bidirectional"))
    )
    (net (code "54") (name "Net-(R24-P$2)") (class "Default")
      (node (ref "R24") (pin "1") (pinfunction "P$2_1") (pintype "bidirectional"))
      (node (ref "U$1") (pin "P$5") (pinfunction "P$5_P$5") (pintype "bidirectional"))
    )
    (net (code "55") (name "Net-(R25-P$2)") (class "Default")
      (node (ref "R25") (pin "1") (pinfunction "P$2_1") (pintype "bidirectional"))
      (node (ref "U$1") (pin "P$8") (pinfunction "P$8_P$8") (pintype "bidirectional"))
    )
    (net (code "56") (name "Net-(R29-P$2)") (class "Default")
      (node (ref "D9") (pin "0") (pinfunction "0_0") (pintype "bidirectional"))
      (node (ref "R29") (pin "1") (pinfunction "P$2_1") (pintype "bidirectional"))
    )
    (net (code "57") (name "Net-(R30-P$2)") (class "Default")
      (node (ref "D8") (pin "0") (pinfunction "0_0") (pintype "bidirectional"))
      (node (ref "R30") (pin "1") (pinfunction "P$2_1") (pintype "bidirectional"))
    )
    (net (code "58") (name "Net-(R31-P$2)") (class "Default")
      (node (ref "D7") (pin "0") (pinfunction "0_0") (pintype "bidirectional"))
      (node (ref "R31") (pin "1") (pinfunction "P$2_1") (pintype "bidirectional"))
    )
    (net (code "59") (name "Net-(R32-P$2)") (class "Default")
      (node (ref "D6") (pin "0") (pinfunction "0_0") (pintype "bidirectional"))
      (node (ref "R32") (pin "1") (pinfunction "P$2_1") (pintype "bidirectional"))
    )
    (net (code "60") (name "Net-(R33-P$2)") (class "Default")
      (node (ref "D5") (pin "0") (pinfunction "0_0") (pintype "bidirectional"))
      (node (ref "R33") (pin "1") (pinfunction "P$2_1") (pintype "bidirectional"))
    )
    (net (code "61") (name "Net-(R34-P$2)") (class "Default")
      (node (ref "D4") (pin "0") (pinfunction "0_0") (pintype "bidirectional"))
      (node (ref "R34") (pin "1") (pinfunction "P$2_1") (pintype "bidirectional"))
    )
    (net (code "62") (name "Net-(R35-P$1)") (class "Default")
      (node (ref "R35") (pin "0") (pinfunction "P$1_0") (pintype "bidirectional"))
      (node (ref "U1") (pin "P$14") (pinfunction "PIO0_3_P$14") (pintype "bidirectional"))
    )
    (net (code "63") (name "Net-(R36-P$1)") (class "Default")
      (node (ref "J4") (pin "P$2") (pinfunction "P$2_P$2") (pintype "bidirectional"))
      (node (ref "R36") (pin "0") (pinfunction "P$1_0") (pintype "bidirectional"))
    )
    (net (code "64") (name "Net-(R37-P$1)") (class "Default")
      (node (ref "J4") (pin "P$3") (pinfunction "P$3_P$3") (pintype "bidirectional"))
      (node (ref "R37") (pin "0") (pinfunction "P$1_0") (pintype "bidirectional"))
    )
    (net (code "65") (name "Net-(R40-P$2)") (class "Default")
      (node (ref "D22") (pin "0") (pinfunction "0_0") (pintype "bidirectional"))
      (node (ref "R40") (pin "1") (pinfunction "P$2_1") (pintype "bidirectional"))
    )
    (net (code "66") (name "Net-(R41-P$2)") (class "Default")
      (node (ref "D21") (pin "0") (pinfunction "0_0") (pintype "bidirectional"))
      (node (ref "R41") (pin "1") (pinfunction "P$2_1") (pintype "bidirectional"))
    )
    (net (code "67") (name "unconnected-(J1-NC-PadP$8)") (class "Default")
      (node (ref "J1") (pin "P$8") (pinfunction "NC_P$8") (pintype "bidirectional"))
    )
    (net (code "68") (name "unconnected-(J1-TDI-PadP$7)") (class "Default")
      (node (ref "J1") (pin "P$7") (pinfunction "TDI_P$7") (pintype "bidirectional"))
    )
    (net (code "69") (name "unconnected-(J1-TDO{slash}SWO-PadP$6)") (class "Default")
      (node (ref "J1") (pin "P$6") (pinfunction "TDO/SWO_P$6") (pintype "bidirectional"))
    )
    (net (code "70") (name "unconnected-(J3-+3V3-PadP$5)") (class "Default")
      (node (ref "J3") (pin "P$5") (pinfunction "+3V3_P$5") (pintype "bidirectional"))
    )
    (net (code "71") (name "unconnected-(U$1-PadP$10)") (class "Default")
      (node (ref "U$1") (pin "P$10") (pinfunction "P$10_P$10") (pintype "bidirectional"))
    )
    (net (code "72") (name "unconnected-(U1-PIO0_1{slash}CLKOUT{slash}CT32B0_MAT2{slash}ISP-PadP$4)") (class "Default")
      (node (ref "U1") (pin "P$4") (pinfunction "PIO0_1/CLKOUT/CT32B0_MAT2/ISP_P$4") (pintype "bidirectional"))
    )
    (net (code "73") (name "unconnected-(U1-PIO0_2{slash}SSEL0{slash}CT16B0_CAP0-PadP$10)") (class "Default")
      (node (ref "U1") (pin "P$10") (pinfunction "PIO0_2/SSEL0/CT16B0_CAP0_P$10") (pintype "bidirectional"))
    )
    (net (code "74") (name "unconnected-(U1-PIO0_9{slash}MOSI0{slash}CT16B0_MAT1-PadP$28)") (class "Default")
      (node (ref "U1") (pin "P$28") (pinfunction "PIO0_9/MOSI0/CT16B0_MAT1_P$28") (pintype "bidirectional"))
    )
    (net (code "75") (name "unconnected-(U1-PIO1_5{slash}RTS{slash}CT32B0_CAP0-PadP$45)") (class "Default")
      (node (ref "U1") (pin "P$45") (pinfunction "PIO1_5/RTS/CT32B0_CAP0_P$45") (pintype "bidirectional"))
    )
    (net (code "76") (name "unconnected-(U1-PIO1_8{slash}CT16B1_CAP0-PadP$9)") (class "Default")
      (node (ref "U1") (pin "P$9") (pinfunction "PIO1_8/CT16B1_CAP0_P$9") (pintype "bidirectional"))
    )
    (net (code "77") (name "unconnected-(U1-PIO1_10{slash}AD6{slash}CT16B1_MAT1-PadP$30)") (class "Default")
      (node (ref "U1") (pin "P$30") (pinfunction "PIO1_10/AD6/CT16B1_MAT1_P$30") (pintype "bidirectional"))
    )
    (net (code "78") (name "unconnected-(U1-PIO1_11{slash}AD7-PadP$42)") (class "Default")
      (node (ref "U1") (pin "P$42") (pinfunction "PIO1_11/AD7_P$42") (pintype "bidirectional"))
    )
    (net (code "79") (name "unconnected-(U1-PIO2_3{slash}RI{slash}MOSI1-PadP$38)") (class "Default")
      (node (ref "U1") (pin "P$38") (pinfunction "PIO2_3/RI/MOSI1_P$38") (pintype "bidirectional"))
    )
    (net (code "80") (name "unconnected-(U1-PIO2_6-PadP$1)") (class "Default")
      (node (ref "U1") (pin "P$1") (pinfunction "PIO2_6_P$1") (pintype "bidirectional"))
    )
    (net (code "81") (name "unconnected-(U1-PIO2_10-PadP$25)") (class "Default")
      (node (ref "U1") (pin "P$25") (pinfunction "PIO2_10_P$25") (pintype "bidirectional"))
    )
    (net (code "82") (name "unconnected-(U1-PIO2_11{slash}SCK0-PadP$31)") (class "Default")
      (node (ref "U1") (pin "P$31") (pinfunction "PIO2_11/SCK0_P$31") (pintype "bidirectional"))
    )
    (net (code "83") (name "unconnected-(U1-PIO3_1{slash}DSR-PadP$37)") (class "Default")
      (node (ref "U1") (pin "P$37") (pinfunction "PIO3_1/DSR_P$37") (pintype "bidirectional"))
    )
    (net (code "84") (name "unconnected-(U1-PIO3_2{slash}DCD-PadP$43)") (class "Default")
      (node (ref "U1") (pin "P$43") (pinfunction "PIO3_2/DCD_P$43") (pintype "bidirectional"))
    )
    (net (code "85") (name "unconnected-(VR1-RESET-Pad2)") (class "Default")
      (node (ref "VR1") (pin "2") (pinfunction "RESET_2") (pintype "bidirectional"))
    )
  )
)
